# PCB_RLB.net
KiCad netlist of a schematic drawn in EAGLE
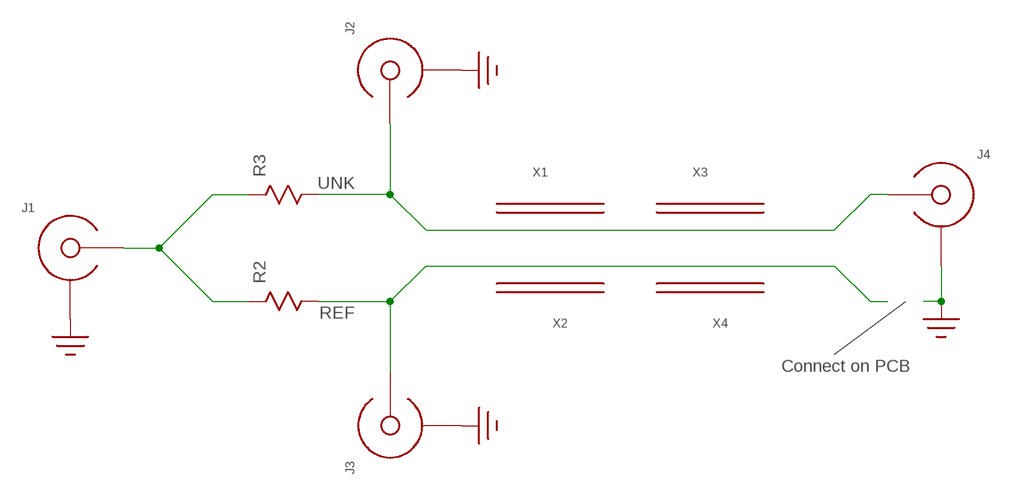
[diagram p0: schematic, sheet 1]

(export (version "E")
  (design (tool "Eeschema 10.0.6"))
  (components
    (comp (ref "J1")
      (value "EDGE_LAUNCH_JACK")
      (footprint "eagle-import:EDGE_LAUNCH_RF_CON")
      (libsource (lib "eagle-import") (part "EDGE_LAUNCH_JACK"))
    )
    (comp (ref "J2")
      (value "EDGE_LAUNCH_JACK")
      (footprint "eagle-import:EDGE_LAUNCH_RF_CON")
      (libsource (lib "eagle-import") (part "EDGE_LAUNCH_JACK"))
    )
    (comp (ref "J3")
      (value "EDGE_LAUNCH_JACK")
      (footprint "eagle-import:EDGE_LAUNCH_RF_CON")
      (libsource (lib "eagle-import") (part "EDGE_LAUNCH_JACK"))
    )
    (comp (ref "J4")
      (value "EDGE_LAUNCH_JACK")
      (footprint "eagle-import:EDGE_LAUNCH_RF_CON")
      (libsource (lib "eagle-import") (part "EDGE_LAUNCH_JACK"))
    )
    (comp (ref "R2")
      (value "R0603")
      (footprint "eagle-import:R0603")
      (libsource (lib "eagle-import") (part "R0603"))
    )
    (comp (ref "R3")
      (value "R0603")
      (footprint "eagle-import:R0603")
      (libsource (lib "eagle-import") (part "R0603"))
    )
    (comp (ref "X1")
      (value "FERRITE_PLATE")
      (footprint "eagle-import:FERRITE-MP0350")
      (libsource (lib "eagle-import") (part "FERRITE_PLATE"))
    )
    (comp (ref "X2")
      (value "FERRITE_PLATE")
      (footprint "eagle-import:FERRITE-MP0350")
      (libsource (lib "eagle-import") (part "FERRITE_PLATE"))
    )
    (comp (ref "X3")
      (value "FERRITE_PLATE")
      (footprint "eagle-import:FERRITE-MP0350")
      (libsource (lib "eagle-import") (part "FERRITE_PLATE"))
    )
    (comp (ref "X4")
      (value "FERRITE_PLATE")
      (footprint "eagle-import:FERRITE-MP0350")
      (libsource (lib "eagle-import") (part "FERRITE_PLATE"))
    )
  )
  (nets
    (net (code "1") (name "/REF") (class "Default")
      (node (ref "J3") (pin "CENTER") (pinfunction "CENTER_CENTER") (pintype "bidirectional"))
      (node (ref "R2") (pin "P$2") (pinfunction "P$4_P$2") (pintype "bidirectional"))
    )
    (net (code "2") (name "/UNK") (class "Default")
      (node (ref "J2") (pin "CENTER") (pinfunction "CENTER_CENTER") (pintype "bidirectional"))
      (node (ref "J4") (pin "CENTER") (pinfunction "CENTER_CENTER") (pintype "bidirectional"))
      (node (ref "R3") (pin "P$2") (pinfunction "P$4_P$2") (pintype "bidirectional"))
    )
    (net (code "3") (name "GND") (class "Default")
      (node (ref "J1") (pin "GND@1") (pinfunction "SHIELD_GND@1") (pintype "bidirectional"))
      (node (ref "J1") (pin "GND@10") (pinfunction "SHIELD_GND@10") (pintype "bidirectional"))
      (node (ref "J1") (pin "GND@11") (pinfunction "SHIELD_GND@11") (pintype "bidirectional"))
      (node (ref "J1") (pin "GND@12") (pinfunction "SHIELD_GND@12") (pintype "bidirectional"))
      (node (ref "J1") (pin "GND@2") (pinfunction "SHIELD_GND@2") (pintype "bidirectional"))
      (node (ref "J1") (pin "GND@3") (pinfunction "SHIELD_GND@3") (pintype "bidirectional"))
      (node (ref "J1") (pin "GND@4") (pinfunction "SHIELD_GND@4") (pintype "bidirectional"))
      (node (ref "J1") (pin "GND@5") (pinfunction "SHIELD_GND@5") (pintype "bidirectional"))
      (node (ref "J1") (pin "GND@6") (pinfunction "SHIELD_GND@6") (pintype "bidirectional"))
      (node (ref "J1") (pin "GND@7") (pinfunction "SHIELD_GND@7") (pintype "bidirectional"))
      (node (ref "J1") (pin "GND@8") (pinfunction "SHIELD_GND@8") (pintype "bidirectional"))
      (node (ref "J1") (pin "GND@9") (pinfunction "SHIELD_GND@9") (pintype "bidirectional"))
      (node (ref "J1") (pin "SHIELD@1") (pinfunction "SHIELD_SHIELD@1") (pintype "bidirectional"))
      (node (ref "J1") (pin "SHIELD@2") (pinfunction "SHIELD_SHIELD@2") (pintype "bidirectional"))
      (node (ref "J2") (pin "GND@1") (pinfunction "SHIELD_GND@1") (pintype "bidirectional"))
      (node (ref "J2") (pin "GND@10") (pinfunction "SHIELD_GND@10") (pintype "bidirectional"))
      (node (ref "J2") (pin "GND@11") (pinfunction "SHIELD_GND@11") (pintype "bidirectional"))
      (node (ref "J2") (pin "GND@12") (pinfunction "SHIELD_GND@12") (pintype "bidirectional"))
      (node (ref "J2") (pin "GND@2") (pinfunction "SHIELD_GND@2") (pintype "bidirectional"))
      (node (ref "J2") (pin "GND@3") (pinfunction "SHIELD_GND@3") (pintype "bidirectional"))
      (node (ref "J2") (pin "GND@4") (pinfunction "SHIELD_GND@4") (pintype "bidirectional"))
      (node (ref "J2") (pin "GND@5") (pinfunction "SHIELD_GND@5") (pintype "bidirectional"))
      (node (ref "J2") (pin "GND@6") (pinfunction "SHIELD_GND@6") (pintype "bidirectional"))
      (node (ref "J2") (pin "GND@7") (pinfunction "SHIELD_GND@7") (pintype "bidirectional"))
      (node (ref "J2") (pin "GND@8") (pinfunction "SHIELD_GND@8") (pintype "bidirectional"))
      (node (ref "J2") (pin "GND@9") (pinfunction "SHIELD_GND@9") (pintype "bidirectional"))
      (node (ref "J2") (pin "SHIELD@1") (pinfunction "SHIELD_SHIELD@1") (pintype "bidirectional"))
      (node (ref "J2") (pin "SHIELD@2") (pinfunction "SHIELD_SHIELD@2") (pintype "bidirectional"))
      (node (ref "J3") (pin "GND@1") (pinfunction "SHIELD_GND@1") (pintype "bidirectional"))
      (node (ref "J3") (pin "GND@10") (pinfunction "SHIELD_GND@10") (pintype "bidirectional"))
      (node (ref "J3") (pin "GND@11") (pinfunction "SHIELD_GND@11") (pintype "bidirectional"))
      (node (ref "J3") (pin "GND@12") (pinfunction "SHIELD_GND@12") (pintype "bidirectional"))
      (node (ref "J3") (pin "GND@2") (pinfunction "SHIELD_GND@2") (pintype "bidirectional"))
      (node (ref "J3") (pin "GND@3") (pinfunction "SHIELD_GND@3") (pintype "bidirectional"))
      (node (ref "J3") (pin "GND@4") (pinfunction "SHIELD_GND@4") (pintype "bidirectional"))
      (node (ref "J3") (pin "GND@5") (pinfunction "SHIELD_GND@5") (pintype "bidirectional"))
      (node (ref "J3") (pin "GND@6") (pinfunction "SHIELD_GND@6") (pintype "bidirectional"))
      (node (ref "J3") (pin "GND@7") (pinfunction "SHIELD_GND@7") (pintype "bidirectional"))
      (node (ref "J3") (pin "GND@8") (pinfunction "SHIELD_GND@8") (pintype "bidirectional"))
      (node (ref "J3") (pin "GND@9") (pinfunction "SHIELD_GND@9") (pintype "bidirectional"))
      (node (ref "J3") (pin "SHIELD@1") (pinfunction "SHIELD_SHIELD@1") (pintype "bidirectional"))
      (node (ref "J3") (pin "SHIELD@2") (pinfunction "SHIELD_SHIELD@2") (pintype "bidirectional"))
      (node (ref "J4") (pin "GND@1") (pinfunction "SHIELD_GND@1") (pintype "bidirectional"))
      (node (ref "J4") (pin "GND@10") (pinfunction "SHIELD_GND@10") (pintype "bidirectional"))
      (node (ref "J4") (pin "GND@11") (pinfunction "SHIELD_GND@11") (pintype "bidirectional"))
      (node (ref "J4") (pin "GND@12") (pinfunction "SHIELD_GND@12") (pintype "bidirectional"))
      (node (ref "J4") (pin "GND@2") (pinfunction "SHIELD_GND@2") (pintype "bidirectional"))
      (node (ref "J4") (pin "GND@3") (pinfunction "SHIELD_GND@3") (pintype "bidirectional"))
      (node (ref "J4") (pin "GND@4") (pinfunction "SHIELD_GND@4") (pintype "bidirectional"))
      (node (ref "J4") (pin "GND@5") (pinfunction "SHIELD_GND@5") (pintype "bidirectional"))
      (node (ref "J4") (pin "GND@6") (pinfunction "SHIELD_GND@6") (pintype "bidirectional"))
      (node (ref "J4") (pin "GND@7") (pinfunction "SHIELD_GND@7") (pintype "bidirectional"))
      (node (ref "J4") (pin "GND@8") (pinfunction "SHIELD_GND@8") (pintype "bidirectional"))
      (node (ref "J4") (pin "GND@9") (pinfunction "SHIELD_GND@9") (pintype "bidirectional"))
      (node (ref "J4") (pin "SHIELD@1") (pinfunction "SHIELD_SHIELD@1") (pintype "bidirectional"))
      (node (ref "J4") (pin "SHIELD@2") (pinfunction "SHIELD_SHIELD@2") (pintype "bidirectional"))
    )
    (net (code "4") (name "Net-(R2-P$3)") (class "Default")
      (node (ref "J1") (pin "CENTER") (pinfunction "CENTER_CENTER") (pintype "bidirectional"))
      (node (ref "R2") (pin "P$1") (pinfunction "P$3_P$1") (pintype "bidirectional"))
      (node (ref "R3") (pin "P$1") (pinfunction "P$3_P$1") (pintype "bidirectional"))
    )
  )
)
